# wisp-5-main.net
KiCad netlist of a schematic drawn in Altium Designer
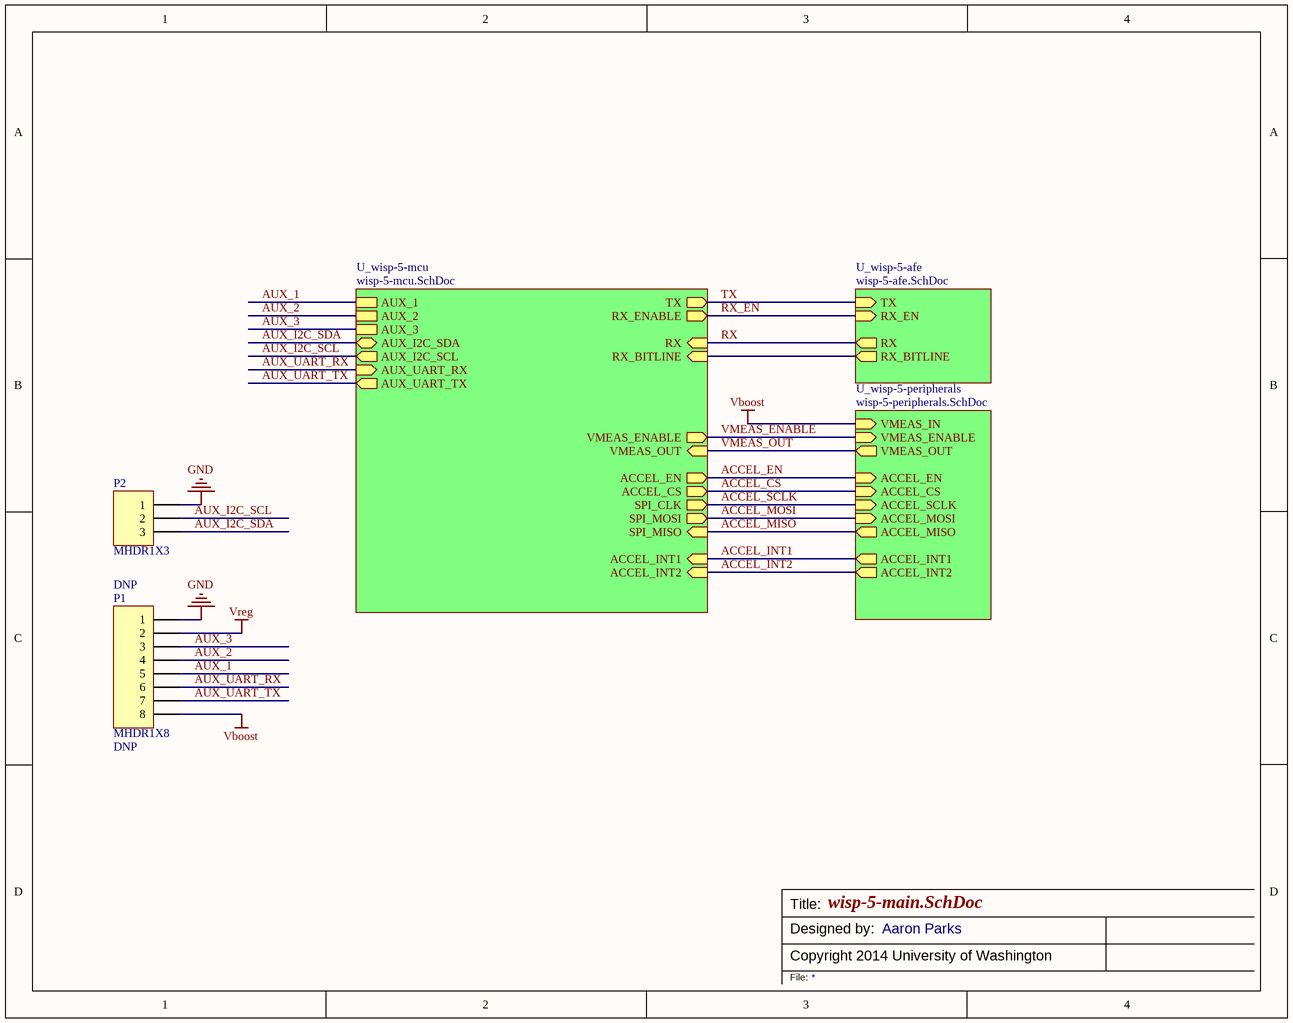
[diagram p0: wisp-5-main.SchDoc]

(export (version "E")
  (design (tool "Eeschema 10.0.6"))
  (components
    (comp (ref "P1")
      (value "MHDR1X8")
      (footprint "MHDR1X8")
      (description "Header, 8-Pin")
      (fields (field (name "DNP") "DNP"))
      (libsource (lib "Miscellaneous Connectors") (part "MHDR1X8"))
    )
    (comp (ref "P2")
      (value "MHDR1X3")
      (footprint "MHDR1X3")
      (description "Header, 3-Pin")
      (fields (field (name "DNP") "DNP"))
      (libsource (lib "Miscellaneous Connectors") (part "MHDR1X3"))
    )
  )
  (nets
    (net (code "8") (name "/AUX_1") (class "Default")
      (node (ref "P1") (pin "5") (pinfunction "5_5") (pintype "passive"))
    )
    (net (code "9") (name "/AUX_2") (class "Default")
      (node (ref "P1") (pin "4") (pinfunction "4_4") (pintype "passive"))
    )
    (net (code "10") (name "/AUX_3") (class "Default")
      (node (ref "P1") (pin "3") (pinfunction "3_3") (pintype "passive"))
    )
    (net (code "11") (name "/AUX_I2C_SCL") (class "Default")
      (node (ref "P2") (pin "2") (pinfunction "2_2") (pintype "passive"))
    )
    (net (code "12") (name "/AUX_I2C_SDA") (class "Default")
      (node (ref "P2") (pin "3") (pinfunction "3_3") (pintype "passive"))
    )
    (net (code "13") (name "/AUX_UART_RX") (class "Default")
      (node (ref "P1") (pin "6") (pinfunction "6_6") (pintype "passive"))
    )
    (net (code "14") (name "/AUX_UART_TX") (class "Default")
      (node (ref "P1") (pin "7") (pinfunction "7_7") (pintype "passive"))
    )
    (net (code "21") (name "GND") (class "Default")
      (node (ref "P1") (pin "1") (pinfunction "1_1") (pintype "passive"))
      (node (ref "P2") (pin "1") (pinfunction "1_1") (pintype "passive"))
    )
    (net (code "22") (name "Vboost") (class "Default")
      (node (ref "P1") (pin "8") (pinfunction "8_8") (pintype "passive"))
    )
    (net (code "23") (name "Vreg") (class "Default")
      (node (ref "P1") (pin "2") (pinfunction "2_2") (pintype "passive"))
    )
  )
)
